# SmartBriefBox.net
KiCad netlist of a schematic drawn in Altium Designer
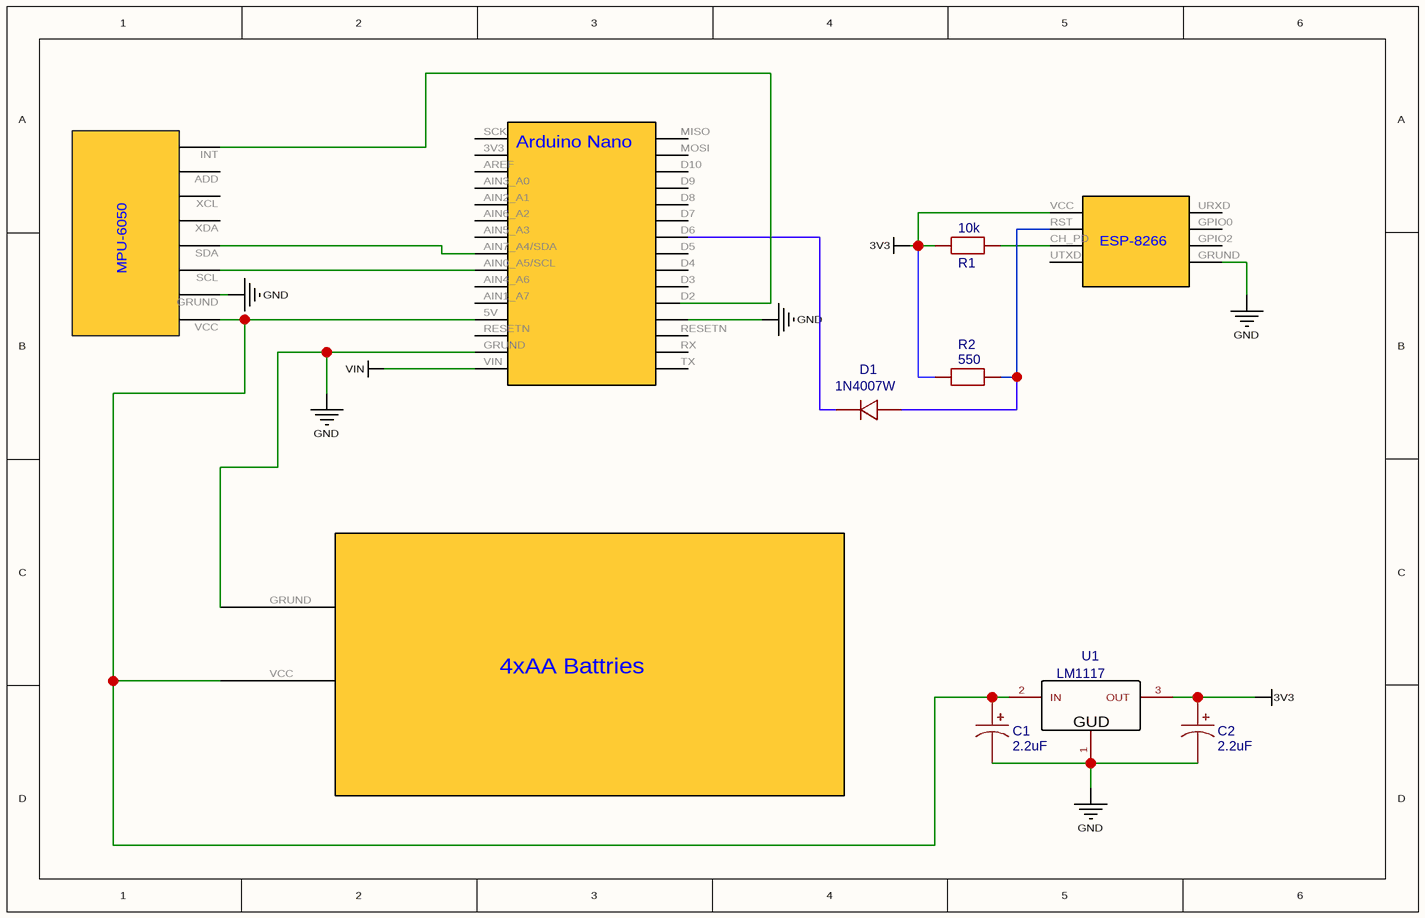
[diagram p0: SmartBriefBox.schdoc]

(export (version "E")
  (design (tool "Eeschema 10.0.6"))
  (components
    (comp (ref "C1")
      (value "2.2uF")
      (fields (field (name "CONTRIBUTOR") "LCEDA_Lib"))
      (libsource (lib "altium-import") (part "root_3_2.2uF_"))
    )
    (comp (ref "C2")
      (value "2.2uF")
      (fields (field (name "CONTRIBUTOR") "LCEDA_Lib"))
      (libsource (lib "altium-import") (part "root_3_2.2uF_"))
    )
    (comp (ref "D1")
      (value "1N4007W")
      (fields (field (name "BOM_SUPPLIER PART") "C328592") (field (name "CONTRIBUTOR") "LCEDA_Lib"))
      (libsource (lib "altium-import") (part "root_2_1N4007W_"))
    )
    (comp (ref "R1")
      (value "10k")
      (fields (field (name "CONTRIBUTOR") "LCEDA_Lib"))
      (libsource (lib "altium-import") (part "root_0_10k_"))
    )
    (comp (ref "R2")
      (value "550")
      (fields (field (name "CONTRIBUTOR") "LCEDA_Lib"))
      (libsource (lib "altium-import") (part "root_0_550_"))
    )
    (comp (ref "U1")
      (value "LM1117")
      (fields
        (field (name "BOM_MANUFACTURER PART") "LM337D2TG")
        (field (name "BOM_SUPPLIER PART") "C146782")
        (field (name "CONTRIBUTOR") "LCEDA_Lib")
      )
      (libsource (lib "altium-import") (part "root_0_LM1117_"))
    )
  )
  (nets
    (net (code "12") (name "/CH_PD") (class "Default")
      (node (ref "R1") (pin "2") (pinfunction "2_2") (pintype "passive"))
    )
    (net (code "27") (name "/RST") (class "Default")
      (node (ref "D1") (pin "2") (pinfunction "2_2") (pintype "passive"))
      (node (ref "R2") (pin "2") (pinfunction "2_2") (pintype "passive"))
    )
    (net (code "37") (name "3V3") (class "Default")
      (node (ref "C1") (pin "1") (pinfunction "1_1") (pintype "passive"))
      (node (ref "C2") (pin "1") (pinfunction "1_1") (pintype "passive"))
      (node (ref "R1") (pin "1") (pinfunction "1_1") (pintype "passive"))
      (node (ref "R2") (pin "1") (pinfunction "1_1") (pintype "passive"))
      (node (ref "U1") (pin "2") (pinfunction "IN_2") (pintype "passive"))
      (node (ref "U1") (pin "3") (pinfunction "OUT_3") (pintype "passive"))
    )
    (net (code "38") (name "GND") (class "Default")
      (node (ref "C1") (pin "2") (pinfunction "2_2") (pintype "passive"))
      (node (ref "C2") (pin "2") (pinfunction "2_2") (pintype "passive"))
      (node (ref "U1") (pin "1") (pinfunction "ADJ_1") (pintype "passive"))
    )
    (net (code "40") (name "unconnected-(D1-Pad1)") (class "Default")
      (node (ref "D1") (pin "1") (pinfunction "1_1") (pintype "passive"))
    )
  )
)
